# Buffered_mult_rev_1.net
KiCad netlist of a schematic drawn in EAGLE
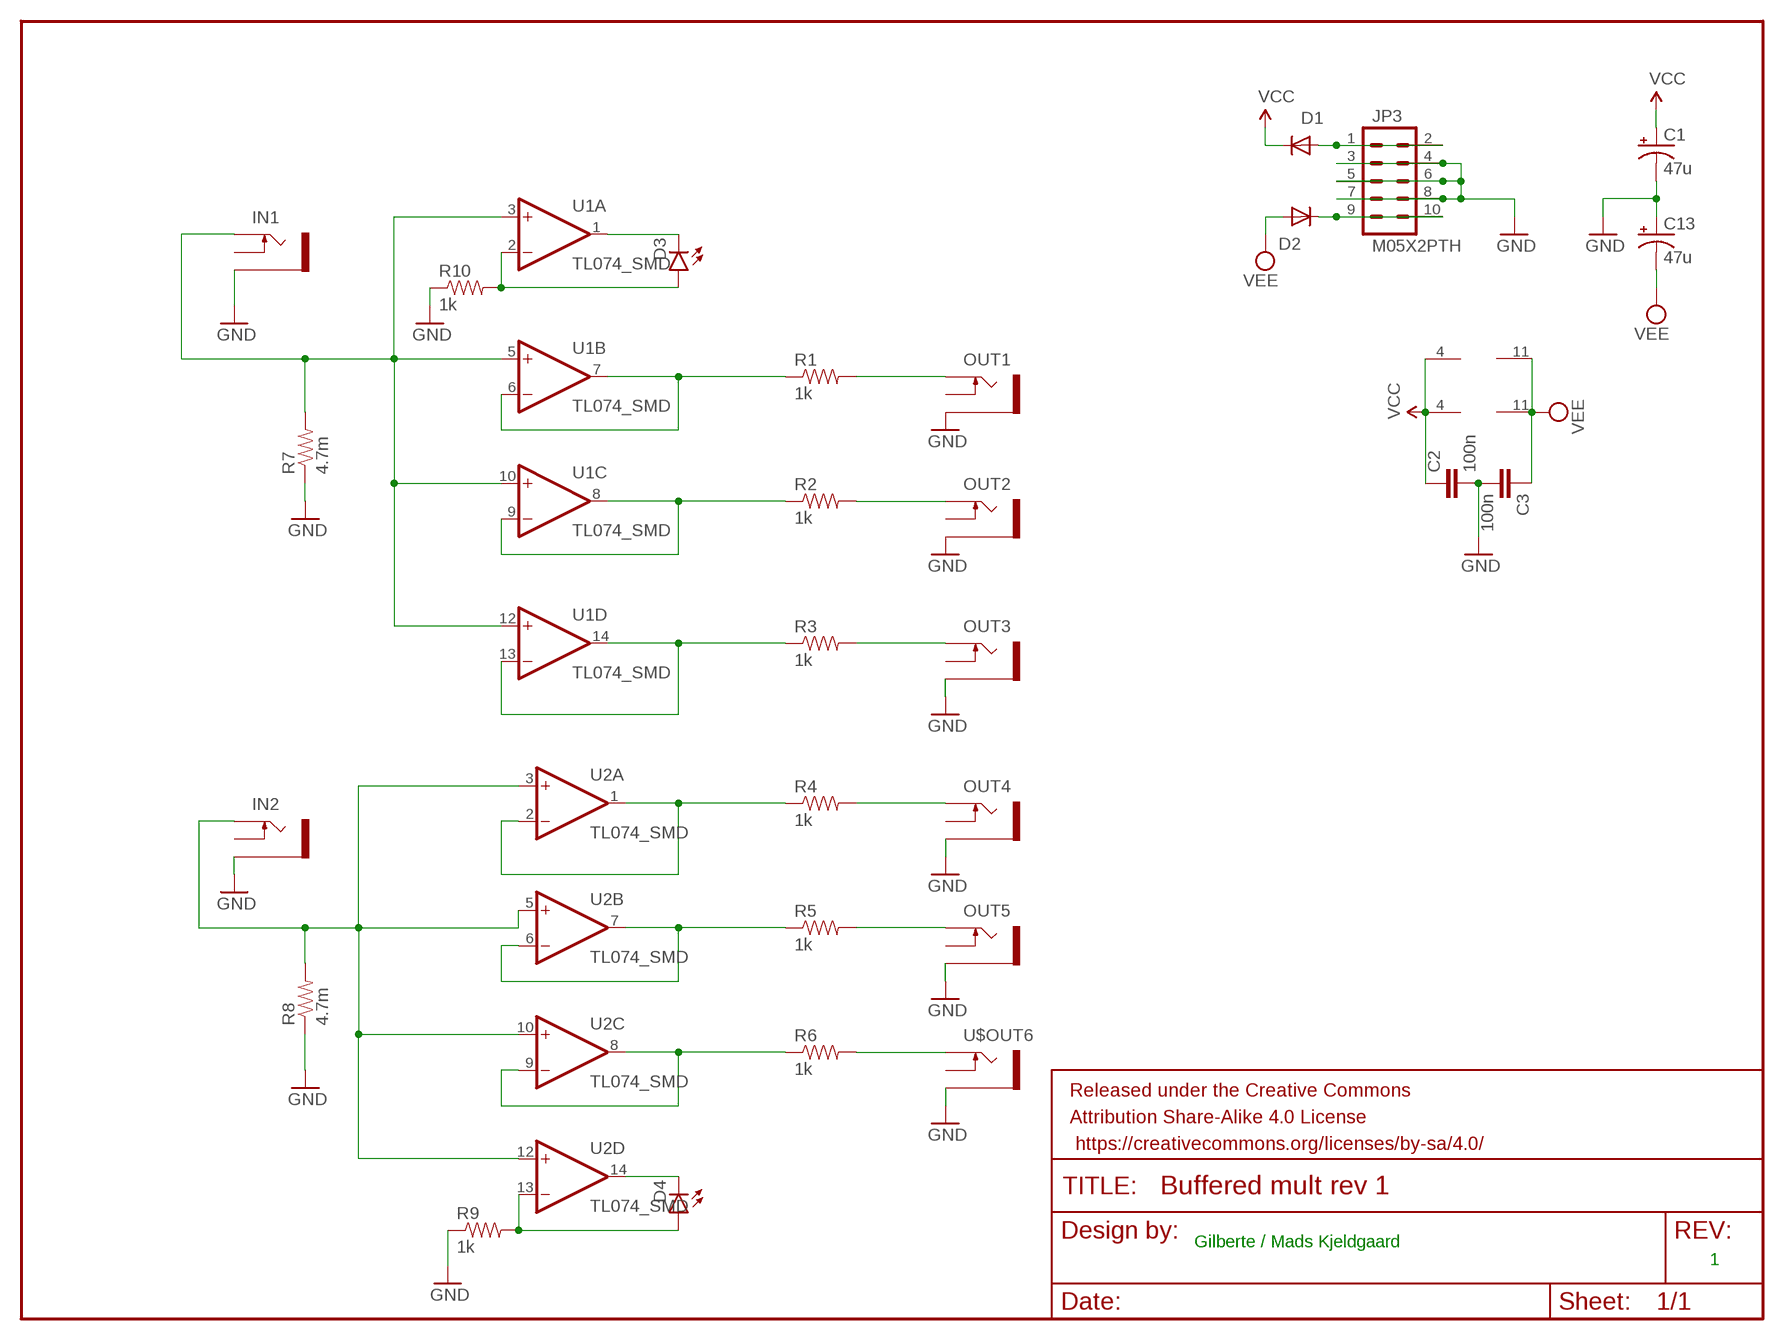
[diagram p0: schematic, sheet 1]

(export (version "E")
  (design (tool "Eeschema 10.0.6"))
  (components
    (comp (ref "C1")
      (value "47u")
      (footprint "eagle-import:PANASONIC_D")
      (libsource (lib "eagle-import") (part "CPOL-USD"))
    )
    (comp (ref "C2")
      (value "100n")
      (footprint "eagle-import:1206")
      (libsource (lib "eagle-import") (part "CAP1206"))
    )
    (comp (ref "C3")
      (value "100n")
      (footprint "eagle-import:1206")
      (libsource (lib "eagle-import") (part "CAP1206"))
    )
    (comp (ref "C13")
      (value "47u")
      (footprint "eagle-import:PANASONIC_D")
      (libsource (lib "eagle-import") (part "CPOL-USD"))
    )
    (comp (ref "D1")
      (value "1N5819HW")
      (footprint "eagle-import:SOD123")
      (libsource (lib "eagle-import") (part "DIODE-SOD123"))
    )
    (comp (ref "D2")
      (value "1N5819HW")
      (footprint "eagle-import:SOD123")
      (libsource (lib "eagle-import") (part "DIODE-SOD123"))
    )
    (comp (ref "D3")
      (value "LED3MM")
      (footprint "eagle-import:LED3MM")
      (libsource (lib "eagle-import") (part "LED3MM"))
    )
    (comp (ref "D4")
      (value "LED3MM")
      (footprint "eagle-import:LED3MM")
      (libsource (lib "eagle-import") (part "LED3MM"))
    )
    (comp (ref "FRAME1")
      (value "FRAME-LETTER")
      (footprint "eagle-import:CREATIVE_COMMONS")
      (libsource (lib "eagle-import") (part "FRAME-LETTER"))
    )
    (comp (ref "IN1")
      (value "THONKICONNOLD")
      (footprint "eagle-import:THONKICONN")
      (libsource (lib "eagle-import") (part "THONKICONNOLD"))
    )
    (comp (ref "IN2")
      (value "THONKICONNOLD")
      (footprint "eagle-import:THONKICONN")
      (libsource (lib "eagle-import") (part "THONKICONNOLD"))
    )
    (comp (ref "JP3")
      (value "M05X2PTH")
      (footprint "eagle-import:AVR_ICSP")
      (libsource (lib "eagle-import") (part "M05X2PTH"))
    )
    (comp (ref "OUT1")
      (value "THONKICONNOLD")
      (footprint "eagle-import:THONKICONN")
      (libsource (lib "eagle-import") (part "THONKICONNOLD"))
    )
    (comp (ref "OUT2")
      (value "THONKICONNOLD")
      (footprint "eagle-import:THONKICONN")
      (libsource (lib "eagle-import") (part "THONKICONNOLD"))
    )
    (comp (ref "OUT3")
      (value "THONKICONNOLD")
      (footprint "eagle-import:THONKICONN")
      (libsource (lib "eagle-import") (part "THONKICONNOLD"))
    )
    (comp (ref "OUT4")
      (value "THONKICONNOLD")
      (footprint "eagle-import:THONKICONN")
      (libsource (lib "eagle-import") (part "THONKICONNOLD"))
    )
    (comp (ref "OUT5")
      (value "THONKICONNOLD")
      (footprint "eagle-import:THONKICONN")
      (libsource (lib "eagle-import") (part "THONKICONNOLD"))
    )
    (comp (ref "R1")
      (value "1k")
      (footprint "eagle-import:1206")
      (libsource (lib "eagle-import") (part "RESISTOR1206"))
    )
    (comp (ref "R2")
      (value "1k")
      (footprint "eagle-import:1206")
      (libsource (lib "eagle-import") (part "RESISTOR1206"))
    )
    (comp (ref "R3")
      (value "1k")
      (footprint "eagle-import:1206")
      (libsource (lib "eagle-import") (part "RESISTOR1206"))
    )
    (comp (ref "R4")
      (value "1k")
      (footprint "eagle-import:1206")
      (libsource (lib "eagle-import") (part "RESISTOR1206"))
    )
    (comp (ref "R5")
      (value "1k")
      (footprint "eagle-import:1206")
      (libsource (lib "eagle-import") (part "RESISTOR1206"))
    )
    (comp (ref "R6")
      (value "1k")
      (footprint "eagle-import:1206")
      (libsource (lib "eagle-import") (part "RESISTOR1206"))
    )
    (comp (ref "R7")
      (value "4.7m")
      (footprint "eagle-import:1206")
      (libsource (lib "eagle-import") (part "RESISTOR1206"))
    )
    (comp (ref "R8")
      (value "4.7m")
      (footprint "eagle-import:1206")
      (libsource (lib "eagle-import") (part "RESISTOR1206"))
    )
    (comp (ref "R9")
      (value "1k")
      (footprint "eagle-import:1206")
      (libsource (lib "eagle-import") (part "RESISTOR1206"))
    )
    (comp (ref "R10")
      (value "1k")
      (footprint "eagle-import:1206")
      (libsource (lib "eagle-import") (part "RESISTOR1206"))
    )
    (comp (ref "U$OUT6")
      (value "THONKICONNOLD")
      (footprint "eagle-import:THONKICONN")
      (libsource (lib "eagle-import") (part "THONKICONNOLD"))
    )
    (comp (ref "U1")
      (value "TL074_SMD")
      (footprint "eagle-import:SO14")
      (libsource (lib "eagle-import") (part "TL074_SMD"))
    )
    (comp (ref "U2")
      (value "TL074_SMD")
      (footprint "eagle-import:SO14")
      (libsource (lib "eagle-import") (part "TL074_SMD"))
    )
  )
  (nets
    (net (code "1") (name "GND") (class "Default")
      (node (ref "C1") (pin "-") (pinfunction "-_-") (pintype "passive"))
      (node (ref "C13") (pin "+") (pinfunction "+_+") (pintype "passive"))
      (node (ref "C2") (pin "2") (pinfunction "2_2") (pintype "passive"))
      (node (ref "C3") (pin "2") (pinfunction "2_2") (pintype "passive"))
      (node (ref "IN1") (pin "P$1_SLEEVE") (pinfunction "SLEEVE_P$1_SLEEVE") (pintype "passive"))
      (node (ref "IN2") (pin "P$1_SLEEVE") (pinfunction "SLEEVE_P$1_SLEEVE") (pintype "passive"))
      (node (ref "JP3") (pin "3") (pinfunction "3_3") (pintype "passive"))
      (node (ref "JP3") (pin "4") (pinfunction "4_4") (pintype "passive"))
      (node (ref "JP3") (pin "5") (pinfunction "5_5") (pintype "passive"))
      (node (ref "JP3") (pin "6") (pinfunction "6_6") (pintype "passive"))
      (node (ref "JP3") (pin "7") (pinfunction "7_7") (pintype "passive"))
      (node (ref "JP3") (pin "8") (pinfunction "8_8") (pintype "passive"))
      (node (ref "OUT1") (pin "P$1_SLEEVE") (pinfunction "SLEEVE_P$1_SLEEVE") (pintype "passive"))
      (node (ref "OUT2") (pin "P$1_SLEEVE") (pinfunction "SLEEVE_P$1_SLEEVE") (pintype "passive"))
      (node (ref "OUT3") (pin "P$1_SLEEVE") (pinfunction "SLEEVE_P$1_SLEEVE") (pintype "passive"))
      (node (ref "OUT4") (pin "P$1_SLEEVE") (pinfunction "SLEEVE_P$1_SLEEVE") (pintype "passive"))
      (node (ref "OUT5") (pin "P$1_SLEEVE") (pinfunction "SLEEVE_P$1_SLEEVE") (pintype "passive"))
      (node (ref "R10") (pin "1") (pinfunction "1_1") (pintype "passive"))
      (node (ref "R7") (pin "1") (pinfunction "1_1") (pintype "passive"))
      (node (ref "R8") (pin "1") (pinfunction "1_1") (pintype "passive"))
      (node (ref "R9") (pin "1") (pinfunction "1_1") (pintype "passive"))
      (node (ref "U$OUT6") (pin "P$1_SLEEVE") (pinfunction "SLEEVE_P$1_SLEEVE") (pintype "passive"))
    )
    (net (code "2") (name "Net-(D1-PadA)") (class "Default")
      (node (ref "D1") (pin "A") (pinfunction "A_A") (pintype "passive"))
      (node (ref "JP3") (pin "1") (pinfunction "1_1") (pintype "passive"))
      (node (ref "JP3") (pin "2") (pinfunction "2_2") (pintype "passive"))
    )
    (net (code "3") (name "Net-(D2-PadC)") (class "Default")
      (node (ref "D2") (pin "C") (pinfunction "C_C") (pintype "passive"))
      (node (ref "JP3") (pin "10") (pinfunction "10_10") (pintype "passive"))
      (node (ref "JP3") (pin "9") (pinfunction "9_9") (pintype "passive"))
    )
    (net (code "4") (name "Net-(D3-C)") (class "Default")
      (node (ref "D3") (pin "K") (pinfunction "C_K") (pintype "passive"))
      (node (ref "U1") (pin "1") (pinfunction "OUT_1") (pintype "output"))
    )
    (net (code "5") (name "Net-(D4-C)") (class "Default")
      (node (ref "D4") (pin "K") (pinfunction "C_K") (pintype "passive"))
      (node (ref "U2") (pin "14") (pinfunction "OUT_14") (pintype "output"))
    )
    (net (code "6") (name "Net-(IN1-TIP)") (class "Default")
      (node (ref "IN1") (pin "P$3_TIP") (pinfunction "TIP_P$3_TIP") (pintype "passive"))
      (node (ref "R7") (pin "2") (pinfunction "2_2") (pintype "passive"))
      (node (ref "U1") (pin "10") (pinfunction "+IN_10") (pintype "input"))
      (node (ref "U1") (pin "12") (pinfunction "+IN_12") (pintype "input"))
      (node (ref "U1") (pin "3") (pinfunction "+IN_3") (pintype "input"))
      (node (ref "U1") (pin "5") (pinfunction "+IN_5") (pintype "input"))
    )
    (net (code "7") (name "Net-(IN2-TIP)") (class "Default")
      (node (ref "IN2") (pin "P$3_TIP") (pinfunction "TIP_P$3_TIP") (pintype "passive"))
      (node (ref "R8") (pin "2") (pinfunction "2_2") (pintype "passive"))
      (node (ref "U2") (pin "10") (pinfunction "+IN_10") (pintype "input"))
      (node (ref "U2") (pin "12") (pinfunction "+IN_12") (pintype "input"))
      (node (ref "U2") (pin "3") (pinfunction "+IN_3") (pintype "input"))
      (node (ref "U2") (pin "5") (pinfunction "+IN_5") (pintype "input"))
    )
    (net (code "8") (name "Net-(OUT1-TIP)") (class "Default")
      (node (ref "OUT1") (pin "P$3_TIP") (pinfunction "TIP_P$3_TIP") (pintype "passive"))
      (node (ref "R1") (pin "2") (pinfunction "2_2") (pintype "passive"))
    )
    (net (code "9") (name "Net-(OUT2-TIP)") (class "Default")
      (node (ref "OUT2") (pin "P$3_TIP") (pinfunction "TIP_P$3_TIP") (pintype "passive"))
      (node (ref "R2") (pin "2") (pinfunction "2_2") (pintype "passive"))
    )
    (net (code "10") (name "Net-(OUT3-TIP)") (class "Default")
      (node (ref "OUT3") (pin "P$3_TIP") (pinfunction "TIP_P$3_TIP") (pintype "passive"))
      (node (ref "R3") (pin "2") (pinfunction "2_2") (pintype "passive"))
    )
    (net (code "11") (name "Net-(OUT4-TIP)") (class "Default")
      (node (ref "OUT4") (pin "P$3_TIP") (pinfunction "TIP_P$3_TIP") (pintype "passive"))
      (node (ref "R4") (pin "2") (pinfunction "2_2") (pintype "passive"))
    )
    (net (code "12") (name "Net-(OUT5-TIP)") (class "Default")
      (node (ref "OUT5") (pin "P$3_TIP") (pinfunction "TIP_P$3_TIP") (pintype "passive"))
      (node (ref "R5") (pin "2") (pinfunction "2_2") (pintype "passive"))
    )
    (net (code "13") (name "Net-(U$OUT6-TIP)") (class "Default")
      (node (ref "R6") (pin "2") (pinfunction "2_2") (pintype "passive"))
      (node (ref "U$OUT6") (pin "P$3_TIP") (pinfunction "TIP_P$3_TIP") (pintype "passive"))
    )
    (net (code "14") (name "Net-(U1A--IN)") (class "Default")
      (node (ref "D3") (pin "A") (pinfunction "A_A") (pintype "passive"))
      (node (ref "R10") (pin "2") (pinfunction "2_2") (pintype "passive"))
      (node (ref "U1") (pin "2") (pinfunction "-IN_2") (pintype "input"))
    )
    (net (code "15") (name "Net-(U1B--IN)") (class "Default")
      (node (ref "R1") (pin "1") (pinfunction "1_1") (pintype "passive"))
      (node (ref "U1") (pin "6") (pinfunction "-IN_6") (pintype "input"))
      (node (ref "U1") (pin "7") (pinfunction "OUT_7") (pintype "output"))
    )
    (net (code "16") (name "Net-(U1C--IN)") (class "Default")
      (node (ref "R2") (pin "1") (pinfunction "1_1") (pintype "passive"))
      (node (ref "U1") (pin "8") (pinfunction "OUT_8") (pintype "output"))
      (node (ref "U1") (pin "9") (pinfunction "-IN_9") (pintype "input"))
    )
    (net (code "17") (name "Net-(U1D--IN)") (class "Default")
      (node (ref "R3") (pin "1") (pinfunction "1_1") (pintype "passive"))
      (node (ref "U1") (pin "13") (pinfunction "-IN_13") (pintype "input"))
      (node (ref "U1") (pin "14") (pinfunction "OUT_14") (pintype "output"))
    )
    (net (code "18") (name "Net-(U2A--IN)") (class "Default")
      (node (ref "R4") (pin "1") (pinfunction "1_1") (pintype "passive"))
      (node (ref "U2") (pin "1") (pinfunction "OUT_1") (pintype "output"))
      (node (ref "U2") (pin "2") (pinfunction "-IN_2") (pintype "input"))
    )
    (net (code "19") (name "Net-(U2B--IN)") (class "Default")
      (node (ref "R5") (pin "1") (pinfunction "1_1") (pintype "passive"))
      (node (ref "U2") (pin "6") (pinfunction "-IN_6") (pintype "input"))
      (node (ref "U2") (pin "7") (pinfunction "OUT_7") (pintype "output"))
    )
    (net (code "20") (name "Net-(U2C--IN)") (class "Default")
      (node (ref "R6") (pin "1") (pinfunction "1_1") (pintype "passive"))
      (node (ref "U2") (pin "8") (pinfunction "OUT_8") (pintype "output"))
      (node (ref "U2") (pin "9") (pinfunction "-IN_9") (pintype "input"))
    )
    (net (code "21") (name "Net-(U2D--IN)") (class "Default")
      (node (ref "D4") (pin "A") (pinfunction "A_A") (pintype "passive"))
      (node (ref "R9") (pin "2") (pinfunction "2_2") (pintype "passive"))
      (node (ref "U2") (pin "13") (pinfunction "-IN_13") (pintype "input"))
    )
    (net (code "22") (name "VCC") (class "Default")
      (node (ref "C1") (pin "+") (pinfunction "+_+") (pintype "passive"))
      (node (ref "C2") (pin "1") (pinfunction "1_1") (pintype "passive"))
      (node (ref "D1") (pin "C") (pinfunction "C_C") (pintype "passive"))
      (node (ref "U1") (pin "4") (pinfunction "V+_4") (pintype "power_in"))
      (node (ref "U2") (pin "4") (pinfunction "V+_4") (pintype "power_in"))
    )
    (net (code "23") (name "VEE") (class "Default")
      (node (ref "C13") (pin "-") (pinfunction "-_-") (pintype "passive"))
      (node (ref "C3") (pin "1") (pinfunction "1_1") (pintype "passive"))
      (node (ref "D2") (pin "A") (pinfunction "A_A") (pintype "passive"))
      (node (ref "U1") (pin "11") (pinfunction "V-_11") (pintype "power_in"))
      (node (ref "U2") (pin "11") (pinfunction "V-_11") (pintype "power_in"))
    )
    (net (code "24") (name "unconnected-(IN1-SWITCH-PadP$2_SWITCH)") (class "Default")
      (node (ref "IN1") (pin "P$2_SWITCH") (pinfunction "SWITCH_P$2_SWITCH") (pintype "passive"))
    )
    (net (code "25") (name "unconnected-(IN2-SWITCH-PadP$2_SWITCH)") (class "Default")
      (node (ref "IN2") (pin "P$2_SWITCH") (pinfunction "SWITCH_P$2_SWITCH") (pintype "passive"))
    )
    (net (code "26") (name "unconnected-(OUT1-SWITCH-PadP$2_SWITCH)") (class "Default")
      (node (ref "OUT1") (pin "P$2_SWITCH") (pinfunction "SWITCH_P$2_SWITCH") (pintype "passive"))
    )
    (net (code "27") (name "unconnected-(OUT2-SWITCH-PadP$2_SWITCH)") (class "Default")
      (node (ref "OUT2") (pin "P$2_SWITCH") (pinfunction "SWITCH_P$2_SWITCH") (pintype "passive"))
    )
    (net (code "28") (name "unconnected-(OUT3-SWITCH-PadP$2_SWITCH)") (class "Default")
      (node (ref "OUT3") (pin "P$2_SWITCH") (pinfunction "SWITCH_P$2_SWITCH") (pintype "passive"))
    )
    (net (code "29") (name "unconnected-(OUT4-SWITCH-PadP$2_SWITCH)") (class "Default")
      (node (ref "OUT4") (pin "P$2_SWITCH") (pinfunction "SWITCH_P$2_SWITCH") (pintype "passive"))
    )
    (net (code "30") (name "unconnected-(OUT5-SWITCH-PadP$2_SWITCH)") (class "Default")
      (node (ref "OUT5") (pin "P$2_SWITCH") (pinfunction "SWITCH_P$2_SWITCH") (pintype "passive"))
    )
    (net (code "31") (name "unconnected-(U$OUT6-SWITCH-PadP$2_SWITCH)") (class "Default")
      (node (ref "U$OUT6") (pin "P$2_SWITCH") (pinfunction "SWITCH_P$2_SWITCH") (pintype "passive"))
    )
  )
)
